# ETH_PHY_RGMII.net
KiCad netlist of a schematic drawn in Altium Designer
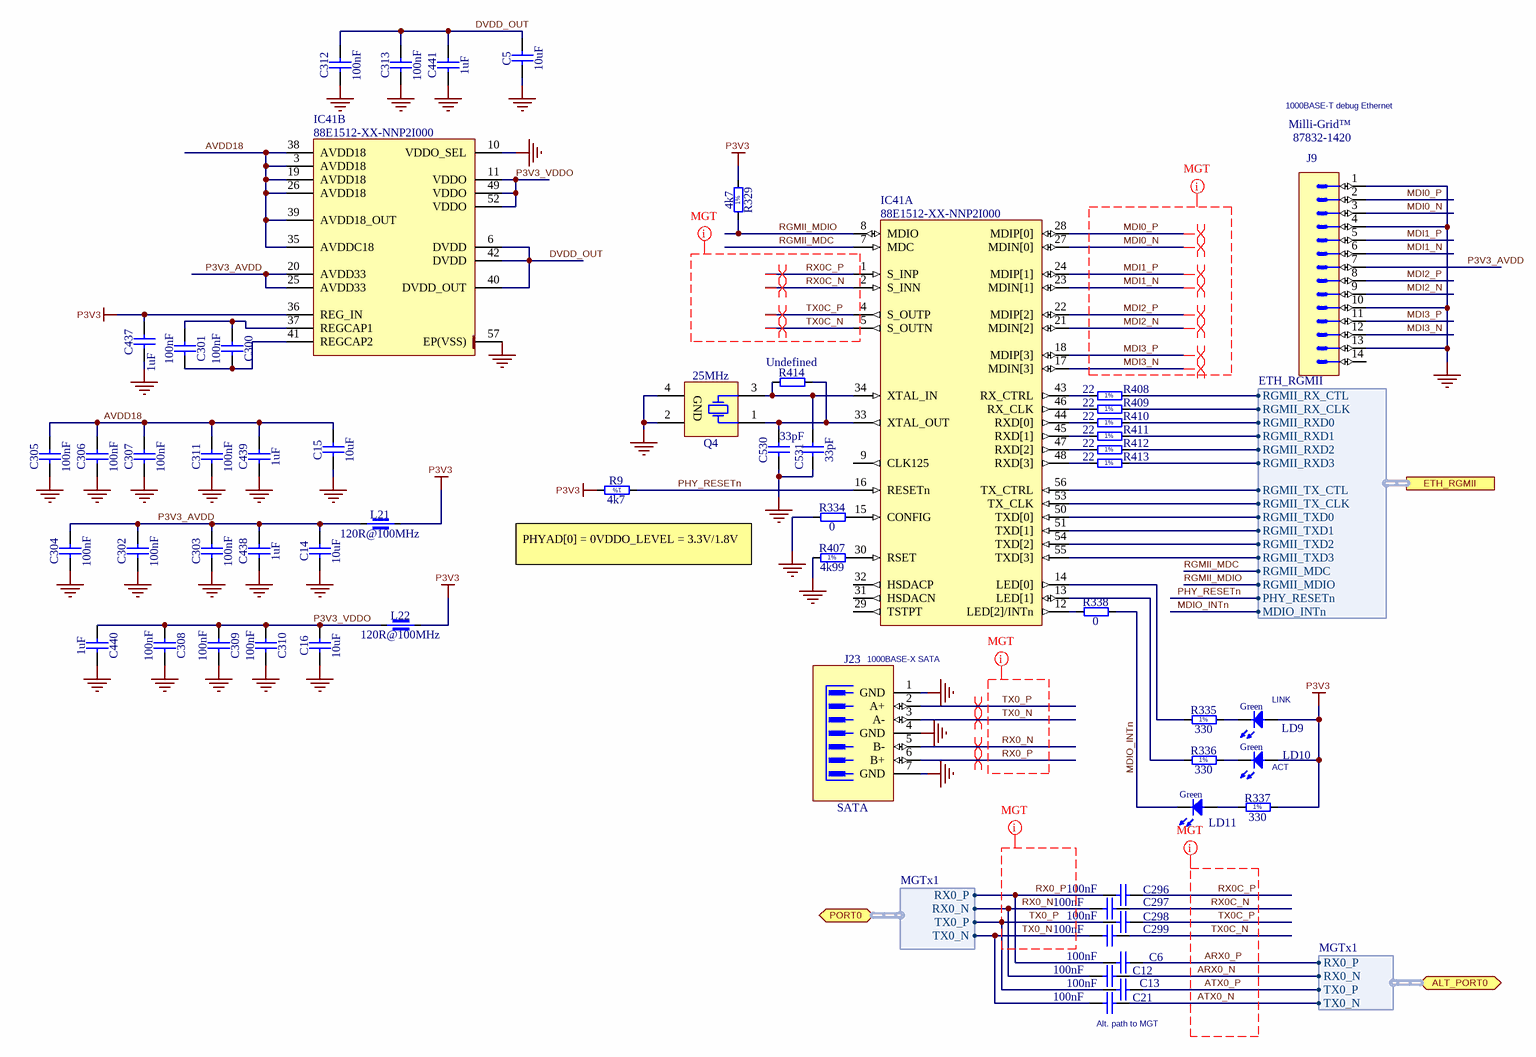
[diagram p0: ETH_PHY_RGMII.SchDoc]

(export (version "E")
  (design (tool "Eeschema 10.0.6"))
  (components
    (comp (ref "C5")
      (value "10uF")
      (footprint "CAPC1608X87N")
      (description "Non-polarised capacitor")
      (fields
        (field (name "MANUFACTURER PART NUMBER") "CC0603_10uF_6.3V_20%_X5R")
        (field (name "MANUFACTURER") "GENERIC")
        (field (name "AUTHOR") "CERN DEM JLC")
      )
      (libsource (lib "Capacitors") (part "Capacitor - non polarized"))
    )
    (comp (ref "C6")
      (value "100nF")
      (footprint "CAPC0603X33N")
      (description "Non-polarised capacitor")
      (fields
        (field (name "MANUFACTURER PART NUMBER") "CC0201_100NF_6.3V_10%_X5R")
        (field (name "MANUFACTURER") "GENERIC")
        (field (name "AUTHOR") "CERN DEM JLC")
      )
      (libsource (lib "Capacitors") (part "Capacitor - non polarized"))
    )
    (comp (ref "C12")
      (value "100nF")
      (footprint "CAPC0603X33N")
      (description "Non-polarised capacitor")
      (fields
        (field (name "MANUFACTURER PART NUMBER") "CC0201_100NF_6.3V_10%_X5R")
        (field (name "MANUFACTURER") "GENERIC")
        (field (name "AUTHOR") "CERN DEM JLC")
      )
      (libsource (lib "Capacitors") (part "Capacitor - non polarized"))
    )
    (comp (ref "C13")
      (value "100nF")
      (footprint "CAPC0603X33N")
      (description "Non-polarised capacitor")
      (fields
        (field (name "MANUFACTURER PART NUMBER") "CC0201_100NF_6.3V_10%_X5R")
        (field (name "MANUFACTURER") "GENERIC")
        (field (name "AUTHOR") "CERN DEM JLC")
      )
      (libsource (lib "Capacitors") (part "Capacitor - non polarized"))
    )
    (comp (ref "C14")
      (value "10uF")
      (footprint "CAPC1608X87N")
      (description "Non-polarised capacitor")
      (fields
        (field (name "MANUFACTURER PART NUMBER") "CC0603_10uF_6.3V_20%_X5R")
        (field (name "MANUFACTURER") "GENERIC")
        (field (name "AUTHOR") "CERN DEM JLC")
      )
      (libsource (lib "Capacitors") (part "Capacitor - non polarized"))
    )
    (comp (ref "C15")
      (value "10uF")
      (footprint "CAPC1608X87N")
      (description "Non-polarised capacitor")
      (fields
        (field (name "MANUFACTURER PART NUMBER") "CC0603_10uF_6.3V_20%_X5R")
        (field (name "MANUFACTURER") "GENERIC")
        (field (name "AUTHOR") "CERN DEM JLC")
      )
      (libsource (lib "Capacitors") (part "Capacitor - non polarized"))
    )
    (comp (ref "C16")
      (value "10uF")
      (footprint "CAPC1608X87N")
      (description "Non-polarised capacitor")
      (fields
        (field (name "MANUFACTURER PART NUMBER") "CC0603_10uF_6.3V_20%_X5R")
        (field (name "MANUFACTURER") "GENERIC")
        (field (name "AUTHOR") "CERN DEM JLC")
      )
      (libsource (lib "Capacitors") (part "Capacitor - non polarized"))
    )
    (comp (ref "C21")
      (value "100nF")
      (footprint "CAPC0603X33N")
      (description "Non-polarised capacitor")
      (fields
        (field (name "MANUFACTURER PART NUMBER") "CC0201_100NF_6.3V_10%_X5R")
        (field (name "MANUFACTURER") "GENERIC")
        (field (name "AUTHOR") "CERN DEM JLC")
      )
      (libsource (lib "Capacitors") (part "Capacitor - non polarized"))
    )
    (comp (ref "C296")
      (value "100nF")
      (footprint "CAPC0603X33N")
      (description "Non-polarised capacitor")
      (fields
        (field (name "MANUFACTURER PART NUMBER") "CC0201_100NF_6.3V_10%_X5R")
        (field (name "MANUFACTURER") "GENERIC")
        (field (name "AUTHOR") "CERN DEM JLC")
      )
      (libsource (lib "Capacitors") (part "Capacitor - non polarized"))
    )
    (comp (ref "C297")
      (value "100nF")
      (footprint "CAPC0603X33N")
      (description "Non-polarised capacitor")
      (fields
        (field (name "MANUFACTURER PART NUMBER") "CC0201_100NF_6.3V_10%_X5R")
        (field (name "MANUFACTURER") "GENERIC")
        (field (name "AUTHOR") "CERN DEM JLC")
      )
      (libsource (lib "Capacitors") (part "Capacitor - non polarized"))
    )
    (comp (ref "C298")
      (value "100nF")
      (footprint "CAPC0603X33N")
      (description "Non-polarised capacitor")
      (fields
        (field (name "MANUFACTURER PART NUMBER") "CC0201_100NF_6.3V_10%_X5R")
        (field (name "MANUFACTURER") "GENERIC")
        (field (name "AUTHOR") "CERN DEM JLC")
      )
      (libsource (lib "Capacitors") (part "Capacitor - non polarized"))
    )
    (comp (ref "C299")
      (value "100nF")
      (footprint "CAPC0603X33N")
      (description "Non-polarised capacitor")
      (fields
        (field (name "MANUFACTURER PART NUMBER") "CC0201_100NF_6.3V_10%_X5R")
        (field (name "MANUFACTURER") "GENERIC")
        (field (name "AUTHOR") "CERN DEM JLC")
      )
      (libsource (lib "Capacitors") (part "Capacitor - non polarized"))
    )
    (comp (ref "C300")
      (value "100nF")
      (footprint "CAPC0603X33N")
      (description "Non-polarised capacitor")
      (fields
        (field (name "MANUFACTURER PART NUMBER") "CC0201_100NF_6.3V_10%_X5R")
        (field (name "MANUFACTURER") "GENERIC")
        (field (name "AUTHOR") "CERN DEM JLC")
      )
      (libsource (lib "Capacitors") (part "Capacitor - non polarized"))
    )
    (comp (ref "C301")
      (value "100nF")
      (footprint "CAPC0603X33N")
      (description "Non-polarised capacitor")
      (fields
        (field (name "MANUFACTURER PART NUMBER") "CC0201_100NF_6.3V_10%_X5R")
        (field (name "MANUFACTURER") "GENERIC")
        (field (name "AUTHOR") "CERN DEM JLC")
      )
      (libsource (lib "Capacitors") (part "Capacitor - non polarized"))
    )
    (comp (ref "C302")
      (value "100nF")
      (footprint "CAPC0603X33N")
      (description "Non-polarised capacitor")
      (fields
        (field (name "MANUFACTURER PART NUMBER") "CC0201_100NF_6.3V_10%_X5R")
        (field (name "MANUFACTURER") "GENERIC")
        (field (name "AUTHOR") "CERN DEM JLC")
      )
      (libsource (lib "Capacitors") (part "Capacitor - non polarized"))
    )
    (comp (ref "C303")
      (value "100nF")
      (footprint "CAPC0603X33N")
      (description "Non-polarised capacitor")
      (fields
        (field (name "MANUFACTURER PART NUMBER") "CC0201_100NF_6.3V_10%_X5R")
        (field (name "MANUFACTURER") "GENERIC")
        (field (name "AUTHOR") "CERN DEM JLC")
      )
      (libsource (lib "Capacitors") (part "Capacitor - non polarized"))
    )
    (comp (ref "C304")
      (value "100nF")
      (footprint "CAPC0603X33N")
      (description "Non-polarised capacitor")
      (fields
        (field (name "MANUFACTURER PART NUMBER") "CC0201_100NF_6.3V_10%_X5R")
        (field (name "MANUFACTURER") "GENERIC")
        (field (name "AUTHOR") "CERN DEM JLC")
      )
      (libsource (lib "Capacitors") (part "Capacitor - non polarized"))
    )
    (comp (ref "C305")
      (value "100nF")
      (footprint "CAPC0603X33N")
      (description "Non-polarised capacitor")
      (fields
        (field (name "MANUFACTURER PART NUMBER") "CC0201_100NF_6.3V_10%_X5R")
        (field (name "MANUFACTURER") "GENERIC")
        (field (name "AUTHOR") "CERN DEM JLC")
      )
      (libsource (lib "Capacitors") (part "Capacitor - non polarized"))
    )
    (comp (ref "C306")
      (value "100nF")
      (footprint "CAPC0603X33N")
      (description "Non-polarised capacitor")
      (fields
        (field (name "MANUFACTURER PART NUMBER") "CC0201_100NF_6.3V_10%_X5R")
        (field (name "MANUFACTURER") "GENERIC")
        (field (name "AUTHOR") "CERN DEM JLC")
      )
      (libsource (lib "Capacitors") (part "Capacitor - non polarized"))
    )
    (comp (ref "C307")
      (value "100nF")
      (footprint "CAPC0603X33N")
      (description "Non-polarised capacitor")
      (fields
        (field (name "MANUFACTURER PART NUMBER") "CC0201_100NF_6.3V_10%_X5R")
        (field (name "MANUFACTURER") "GENERIC")
        (field (name "AUTHOR") "CERN DEM JLC")
      )
      (libsource (lib "Capacitors") (part "Capacitor - non polarized"))
    )
    (comp (ref "C308")
      (value "100nF")
      (footprint "CAPC0603X33N")
      (description "Non-polarised capacitor")
      (fields
        (field (name "MANUFACTURER PART NUMBER") "CC0201_100NF_6.3V_10%_X5R")
        (field (name "MANUFACTURER") "GENERIC")
        (field (name "AUTHOR") "CERN DEM JLC")
      )
      (libsource (lib "Capacitors") (part "Capacitor - non polarized"))
    )
    (comp (ref "C309")
      (value "100nF")
      (footprint "CAPC0603X33N")
      (description "Non-polarised capacitor")
      (fields
        (field (name "MANUFACTURER PART NUMBER") "CC0201_100NF_6.3V_10%_X5R")
        (field (name "MANUFACTURER") "GENERIC")
        (field (name "AUTHOR") "CERN DEM JLC")
      )
      (libsource (lib "Capacitors") (part "Capacitor - non polarized"))
    )
    (comp (ref "C310")
      (value "100nF")
      (footprint "CAPC0603X33N")
      (description "Non-polarised capacitor")
      (fields
        (field (name "MANUFACTURER PART NUMBER") "CC0201_100NF_6.3V_10%_X5R")
        (field (name "MANUFACTURER") "GENERIC")
        (field (name "AUTHOR") "CERN DEM JLC")
      )
      (libsource (lib "Capacitors") (part "Capacitor - non polarized"))
    )
    (comp (ref "C311")
      (value "100nF")
      (footprint "CAPC0603X33N")
      (description "Non-polarised capacitor")
      (fields
        (field (name "MANUFACTURER PART NUMBER") "CC0201_100NF_6.3V_10%_X5R")
        (field (name "MANUFACTURER") "GENERIC")
        (field (name "AUTHOR") "CERN DEM JLC")
      )
      (libsource (lib "Capacitors") (part "Capacitor - non polarized"))
    )
    (comp (ref "C312")
      (value "100nF")
      (footprint "CAPC0603X33N")
      (description "Non-polarised capacitor")
      (fields
        (field (name "MANUFACTURER PART NUMBER") "CC0201_100NF_6.3V_10%_X5R")
        (field (name "MANUFACTURER") "GENERIC")
        (field (name "AUTHOR") "CERN DEM JLC")
      )
      (libsource (lib "Capacitors") (part "Capacitor - non polarized"))
    )
    (comp (ref "C313")
      (value "100nF")
      (footprint "CAPC0603X33N")
      (description "Non-polarised capacitor")
      (fields
        (field (name "MANUFACTURER PART NUMBER") "CC0201_100NF_6.3V_10%_X5R")
        (field (name "MANUFACTURER") "GENERIC")
        (field (name "AUTHOR") "CERN DEM JLC")
      )
      (libsource (lib "Capacitors") (part "Capacitor - non polarized"))
    )
    (comp (ref "C437")
      (value "1uF")
      (footprint "CAPC1005X55N")
      (description "Non-polarised capacitor")
      (fields
        (field (name "MANUFACTURER PART NUMBER") "CC0402_1UF_16V_10%_X5R")
        (field (name "MANUFACTURER") "GENERIC")
        (field (name "AUTHOR") "CERN DEM JLC")
      )
      (libsource (lib "Capacitors") (part "Capacitor - non polarized"))
    )
    (comp (ref "C438")
      (value "1uF")
      (footprint "CAPC1005X55N")
      (description "Non-polarised capacitor")
      (fields
        (field (name "MANUFACTURER PART NUMBER") "CC0402_1UF_16V_10%_X5R")
        (field (name "MANUFACTURER") "GENERIC")
        (field (name "AUTHOR") "CERN DEM JLC")
      )
      (libsource (lib "Capacitors") (part "Capacitor - non polarized"))
    )
    (comp (ref "C439")
      (value "1uF")
      (footprint "CAPC1005X55N")
      (description "Non-polarised capacitor")
      (fields
        (field (name "MANUFACTURER PART NUMBER") "CC0402_1UF_16V_10%_X5R")
        (field (name "MANUFACTURER") "GENERIC")
        (field (name "AUTHOR") "CERN DEM JLC")
      )
      (libsource (lib "Capacitors") (part "Capacitor - non polarized"))
    )
    (comp (ref "C440")
      (value "1uF")
      (footprint "CAPC1005X55N")
      (description "Non-polarised capacitor")
      (fields
        (field (name "MANUFACTURER PART NUMBER") "CC0402_1UF_16V_10%_X5R")
        (field (name "MANUFACTURER") "GENERIC")
        (field (name "AUTHOR") "CERN DEM JLC")
      )
      (libsource (lib "Capacitors") (part "Capacitor - non polarized"))
    )
    (comp (ref "C441")
      (value "1uF")
      (footprint "CAPC1005X55N")
      (description "Non-polarised capacitor")
      (fields
        (field (name "MANUFACTURER PART NUMBER") "CC0402_1UF_16V_10%_X5R")
        (field (name "MANUFACTURER") "GENERIC")
        (field (name "AUTHOR") "CERN DEM JLC")
      )
      (libsource (lib "Capacitors") (part "Capacitor - non polarized"))
    )
    (comp (ref "C530")
      (value "33pF")
      (footprint "CAPC1005X55N")
      (description "Non-polarised capacitor")
      (fields
        (field (name "MANUFACTURER PART NUMBER") "CC0402_33PF_50V_5%_C0G")
        (field (name "MANUFACTURER") "GENERIC")
        (field (name "AUTHOR") "CERN DEM JLC")
      )
      (libsource (lib "Capacitors") (part "Capacitor - non polarized"))
    )
    (comp (ref "C531")
      (value "33pF")
      (footprint "CAPC1005X55N")
      (description "Non-polarised capacitor")
      (fields
        (field (name "MANUFACTURER PART NUMBER") "CC0402_33PF_50V_5%_C0G")
        (field (name "MANUFACTURER") "GENERIC")
        (field (name "AUTHOR") "CERN DEM JLC")
      )
      (libsource (lib "Capacitors") (part "Capacitor - non polarized"))
    )
    (comp (ref "IC41")
      (value "88E1512-XX-NNP2I000")
      (footprint "QFN50P800X800X100-57N-S437")
      (description "Alaska Integrated 10/100/1000 Mbps Energy Efficient Ethernet Transceiver")
      (fields (field (name "MANUFACTURER") "MARVELL  TECHNOLOGY") (field (name "AUTHOR") "CERN DEM JLC"))
      (libsource (lib "ICs And Semiconductors") (part "88E1512-XX-NNP2I000"))
    )
    (comp (ref "J9")
      (value "Milli-Grid™")
      (footprint "MOLEX_87832-1420")
      (description "Connector 14 Male")
      (fields
        (field (name "MANUFACTURER PART NUMBER") "87832-1420")
        (field (name "MANUFACTURER") "MOLEX")
        (field (name "PART NUMBER") "MOLEX_87832-1420")
        (field (name "AUTHOR") "CERN DEM JLC")
      )
      (libsource (lib "Connectors") (part "Connector 14 Male"))
    )
    (comp (ref "J23")
      (value "SATA")
      (footprint "MOLEX_67800-5005")
      (description "7 Pin SATA Receptacle")
      (fields
        (field (name "PART NUMBER") "MOLEX_67800-5005")
        (field (name "MANUFACTURER") "MOLEX")
        (field (name "AUTHOR") "CERN DEM MR")
      )
      (libsource (lib "Connectors") (part "Connector SATA 7 Male"))
    )
    (comp (ref "L21")
      (value "120R@100MHz")
      (footprint "INDC1005X55N")
      (fields
        (field (name "MANUFACTURER PART NUMBER") "BLM15PX121SN1D")
        (field (name "MANUFACTURER") "MURATA")
        (field (name "PART NUMBER") "IND0402_MURATA_BLM15PX121SN1D")
        (field (name "AUTHOR") "CERN DEM JMW")
      )
      (libsource (lib "") (part "Ferrite Bead_1"))
    )
    (comp (ref "L22")
      (value "120R@100MHz")
      (footprint "INDC1005X55N")
      (fields
        (field (name "MANUFACTURER PART NUMBER") "BLM15PX121SN1D")
        (field (name "MANUFACTURER") "MURATA")
        (field (name "PART NUMBER") "IND0402_MURATA_BLM15PX121SN1D")
        (field (name "AUTHOR") "CERN DEM JMW")
      )
      (libsource (lib "Inductors & Transformers") (part "Ferrite Bead"))
    )
    (comp (ref "LD9")
      (value "Green")
      (footprint "LED_AVAGO_HSME-C120")
      (description "LED Green 1C 2A")
      (fields
        (field (name "MANUFACTURER PART NUMBER") "HSME-C120")
        (field (name "MANUFACTURER") "AVAGO TECHNOLOGIES")
        (field (name "AUTHOR") "CERN DEM JMW")
      )
      (libsource (lib "ICs And Semiconductors") (part "LED Green 1C 2A"))
    )
    (comp (ref "LD10")
      (value "Green")
      (footprint "LED_AVAGO_HSME-C120")
      (description "LED Green 1C 2A")
      (fields
        (field (name "MANUFACTURER PART NUMBER") "HSME-C120")
        (field (name "MANUFACTURER") "AVAGO TECHNOLOGIES")
        (field (name "AUTHOR") "CERN DEM JMW")
      )
      (libsource (lib "ICs And Semiconductors") (part "LED Green 1C 2A"))
    )
    (comp (ref "LD11")
      (value "Green")
      (footprint "LED_AVAGO_HSME-C120")
      (description "LED Green 1C 2A")
      (fields
        (field (name "MANUFACTURER PART NUMBER") "HSME-C120")
        (field (name "MANUFACTURER") "AVAGO TECHNOLOGIES")
        (field (name "AUTHOR") "CERN DEM JMW")
      )
      (libsource (lib "ICs And Semiconductors") (part "LED Green 1C 2A"))
    )
    (comp (ref "Q4")
      (value "25MHz")
      (footprint "XTAL_TXC_8Y")
      (description "Crystal 4 pins 1=XTAL Control 2=GND3=XTAL 4=GND")
      (fields
        (field (name "MANUFACTURER PART NUMBER") "8Y-25.000MAAJ-T")
        (field (name "MANUFACTURER") "TXC CORPORATION")
        (field (name "AUTHOR") "CERN DEM JLC")
      )
      (libsource (lib "ICs And Semiconductors") (part "Quartz Crystal 1X 2GND 3X 4GND"))
    )
    (comp (ref "R9")
      (value "4k7")
      (footprint "RESC1005X40N")
      (description "Resistor - 1%")
      (fields
        (field (name "MANUFACTURER PART NUMBER") "R0402_4K7_1%_0.0625W_100PPM")
        (field (name "MANUFACTURER") "GENERIC")
        (field (name "AUTHOR") "CERN DEM JLC")
      )
      (libsource (lib "Resistors") (part "Resistor - 1%"))
    )
    (comp (ref "R329")
      (value "4k7")
      (footprint "RESC1005X40N")
      (description "Resistor - 1%")
      (fields
        (field (name "MANUFACTURER PART NUMBER") "R0402_4K7_1%_0.0625W_100PPM")
        (field (name "MANUFACTURER") "GENERIC")
        (field (name "AUTHOR") "CERN DEM JLC")
      )
      (libsource (lib "Resistors") (part "Resistor - 1%"))
    )
    (comp (ref "R334")
      (value "0")
      (footprint "RESC1005X40N")
      (description "Resistor")
      (fields
        (field (name "MANUFACTURER PART NUMBER") "R0402_0R_JUMPER")
        (field (name "MANUFACTURER") "GENERIC")
        (field (name "AUTHOR") "CERN DEM JLC")
      )
      (libsource (lib "Resistors") (part "Resistor"))
    )
    (comp (ref "R335")
      (value "330")
      (footprint "RESC1005X40N")
      (description "Resistor - 1%")
      (fields
        (field (name "MANUFACTURER PART NUMBER") "R0402_330R_1%_0.0625W_100PPM")
        (field (name "MANUFACTURER") "GENERIC")
        (field (name "AUTHOR") "CERN DEM JLC")
      )
      (libsource (lib "Resistors") (part "Resistor - 1%"))
    )
    (comp (ref "R336")
      (value "330")
      (footprint "RESC1005X40N")
      (description "Resistor - 1%")
      (fields
        (field (name "MANUFACTURER PART NUMBER") "R0402_330R_1%_0.0625W_100PPM")
        (field (name "MANUFACTURER") "GENERIC")
        (field (name "AUTHOR") "CERN DEM JLC")
      )
      (libsource (lib "Resistors") (part "Resistor - 1%"))
    )
    (comp (ref "R337")
      (value "330")
      (footprint "RESC1005X40N")
      (description "Resistor - 1%")
      (fields
        (field (name "MANUFACTURER PART NUMBER") "R0402_330R_1%_0.0625W_100PPM")
        (field (name "MANUFACTURER") "GENERIC")
        (field (name "AUTHOR") "CERN DEM JLC")
      )
      (libsource (lib "Resistors") (part "Resistor - 1%"))
    )
    (comp (ref "R338")
      (value "0")
      (footprint "RESC1005X40N")
      (description "Resistor")
      (fields
        (field (name "MANUFACTURER PART NUMBER") "R0402_0R_JUMPER")
        (field (name "MANUFACTURER") "GENERIC")
        (field (name "AUTHOR") "CERN DEM JLC")
      )
      (libsource (lib "Resistors") (part "Resistor"))
    )
    (comp (ref "R407")
      (value "4k99")
      (footprint "RESC1608X55N")
      (description "Resistor - 1%")
      (fields
        (field (name "MANUFACTURER PART NUMBER") "R0603_4K99_1%_0.063W_50PPM")
        (field (name "MANUFACTURER") "GENERIC")
        (field (name "AUTHOR") "CERN DEM JLC")
      )
      (libsource (lib "Resistors") (part "Resistor - 1%"))
    )
    (comp (ref "R408")
      (value "22")
      (footprint "RESC1005X40N")
      (description "Resistor - 1%")
      (fields
        (field (name "MANUFACTURER PART NUMBER") "R0402_22R_1%_0.0625W_100PPM")
        (field (name "MANUFACTURER") "GENERIC")
        (field (name "AUTHOR") "CERN DEM JLC")
      )
      (libsource (lib "Resistors") (part "Resistor - 1%"))
    )
    (comp (ref "R409")
      (value "22")
      (footprint "RESC1005X40N")
      (description "Resistor - 1%")
      (fields
        (field (name "MANUFACTURER PART NUMBER") "R0402_22R_1%_0.0625W_100PPM")
        (field (name "MANUFACTURER") "GENERIC")
        (field (name "AUTHOR") "CERN DEM JLC")
      )
      (libsource (lib "Resistors") (part "Resistor - 1%"))
    )
    (comp (ref "R410")
      (value "22")
      (footprint "RESC1005X40N")
      (description "Resistor - 1%")
      (fields
        (field (name "MANUFACTURER PART NUMBER") "R0402_22R_1%_0.0625W_100PPM")
        (field (name "MANUFACTURER") "GENERIC")
        (field (name "AUTHOR") "CERN DEM JLC")
      )
      (libsource (lib "Resistors") (part "Resistor - 1%"))
    )
    (comp (ref "R411")
      (value "22")
      (footprint "RESC1005X40N")
      (description "Resistor - 1%")
      (fields
        (field (name "MANUFACTURER PART NUMBER") "R0402_22R_1%_0.0625W_100PPM")
        (field (name "MANUFACTURER") "GENERIC")
        (field (name "AUTHOR") "CERN DEM JLC")
      )
      (libsource (lib "Resistors") (part "Resistor - 1%"))
    )
    (comp (ref "R412")
      (value "22")
      (footprint "RESC1005X40N")
      (description "Resistor - 1%")
      (fields
        (field (name "MANUFACTURER PART NUMBER") "R0402_22R_1%_0.0625W_100PPM")
        (field (name "MANUFACTURER") "GENERIC")
        (field (name "AUTHOR") "CERN DEM JLC")
      )
      (libsource (lib "Resistors") (part "Resistor - 1%"))
    )
    (comp (ref "R413")
      (value "22")
      (footprint "RESC1005X40N")
      (description "Resistor - 1%")
      (fields
        (field (name "MANUFACTURER PART NUMBER") "R0402_22R_1%_0.0625W_100PPM")
        (field (name "MANUFACTURER") "GENERIC")
        (field (name "AUTHOR") "CERN DEM JLC")
      )
      (libsource (lib "Resistors") (part "Resistor - 1%"))
    )
    (comp (ref "R414")
      (value "Undefined")
      (footprint "RESC1005X40N")
      (description "Resistor")
      (fields
        (field (name "MANUFACTURER PART NUMBER") "R0402_NO-VALUE")
        (field (name "AUTHOR") "CERN DEM JLC")
      )
      (libsource (lib "Resistors") (part "Resistor"))
    )
  )
  (nets
    (net (code "3") (name "/ARX0_N") (class "Default")
      (node (ref "C12") (pin "2") (pinfunction "2_2") (pintype "passive"))
    )
    (net (code "4") (name "/ARX0_P") (class "Default")
      (node (ref "C6") (pin "2") (pinfunction "2_2") (pintype "passive"))
    )
    (net (code "5") (name "/ATX0_N") (class "Default")
      (node (ref "C21") (pin "2") (pinfunction "2_2") (pintype "passive"))
    )
    (net (code "6") (name "/ATX0_P") (class "Default")
      (node (ref "C13") (pin "2") (pinfunction "2_2") (pintype "passive"))
    )
    (net (code "7") (name "/AVDD18") (class "Default")
      (node (ref "C15") (pin "2") (pinfunction "2_2") (pintype "passive"))
      (node (ref "C305") (pin "2") (pinfunction "2_2") (pintype "passive"))
      (node (ref "C306") (pin "2") (pinfunction "2_2") (pintype "passive"))
      (node (ref "C307") (pin "2") (pinfunction "2_2") (pintype "passive"))
      (node (ref "C311") (pin "2") (pinfunction "2_2") (pintype "passive"))
      (node (ref "C439") (pin "2") (pinfunction "2_2") (pintype "passive"))
      (node (ref "IC41") (pin "19") (pinfunction "AVDD18_19") (pintype "power_in"))
      (node (ref "IC41") (pin "26") (pinfunction "AVDD18_26") (pintype "power_in"))
      (node (ref "IC41") (pin "3") (pinfunction "AVDD18_3") (pintype "power_in"))
      (node (ref "IC41") (pin "35") (pinfunction "AVDDC18_35") (pintype "power_in"))
      (node (ref "IC41") (pin "38") (pinfunction "AVDD18_38") (pintype "power_in"))
      (node (ref "IC41") (pin "39") (pinfunction "AVDD18_OUT_39") (pintype "power_in"))
    )
    (net (code "8") (name "/DVDD_OUT") (class "Default")
      (node (ref "C312") (pin "2") (pinfunction "2_2") (pintype "passive"))
      (node (ref "C313") (pin "2") (pinfunction "2_2") (pintype "passive"))
      (node (ref "C441") (pin "2") (pinfunction "2_2") (pintype "passive"))
      (node (ref "C5") (pin "2") (pinfunction "2_2") (pintype "passive"))
      (node (ref "IC41") (pin "40") (pinfunction "DVDD_OUT_40") (pintype "power_in"))
      (node (ref "IC41") (pin "42") (pinfunction "DVDD_42") (pintype "power_in"))
      (node (ref "IC41") (pin "6") (pinfunction "DVDD_6") (pintype "power_in"))
    )
    (net (code "9") (name "/MDI0_N") (class "Default")
      (node (ref "IC41") (pin "27") (pinfunction "MDIN[0]_27") (pintype "bidirectional"))
      (node (ref "J9") (pin "3") (pinfunction "3_3") (pintype "bidirectional"))
    )
    (net (code "10") (name "/MDI0_P") (class "Default")
      (node (ref "IC41") (pin "28") (pinfunction "MDIP[0]_28") (pintype "bidirectional"))
      (node (ref "J9") (pin "2") (pinfunction "2_2") (pintype "bidirectional"))
    )
    (net (code "11") (name "/MDI1_N") (class "Default")
      (node (ref "IC41") (pin "23") (pinfunction "MDIN[1]_23") (pintype "bidirectional"))
      (node (ref "J9") (pin "6") (pinfunction "6_6") (pintype "bidirectional"))
    )
    (net (code "12") (name "/MDI1_P") (class "Default")
      (node (ref "IC41") (pin "24") (pinfunction "MDIP[1]_24") (pintype "bidirectional"))
      (node (ref "J9") (pin "5") (pinfunction "5_5") (pintype "bidirectional"))
    )
    (net (code "13") (name "/MDI2_N") (class "Default")
      (node (ref "IC41") (pin "21") (pinfunction "MDIN[2]_21") (pintype "bidirectional"))
      (node (ref "J9") (pin "9") (pinfunction "9_9") (pintype "bidirectional"))
    )
    (net (code "14") (name "/MDI2_P") (class "Default")
      (node (ref "IC41") (pin "22") (pinfunction "MDIP[2]_22") (pintype "bidirectional"))
      (node (ref "J9") (pin "8") (pinfunction "8_8") (pintype "bidirectional"))
    )
    (net (code "15") (name "/MDI3_N") (class "Default")
      (node (ref "IC41") (pin "17") (pinfunction "MDIN[3]_17") (pintype "bidirectional"))
      (node (ref "J9") (pin "12") (pinfunction "12_12") (pintype "bidirectional"))
    )
    (net (code "16") (name "/MDI3_P") (class "Default")
      (node (ref "IC41") (pin "18") (pinfunction "MDIP[3]_18") (pintype "bidirectional"))
      (node (ref "J9") (pin "11") (pinfunction "11_11") (pintype "bidirectional"))
    )
    (net (code "17") (name "/MDIO_INTn") (class "Default")
      (node (ref "LD11") (pin "1") (pinfunction "C_1") (pintype "passive"))
      (node (ref "R338") (pin "2") (pinfunction "2_2") (pintype "passive"))
    )
    (net (code "18") (name "/P3V3_AVDD") (class "Default")
      (node (ref "C14") (pin "2") (pinfunction "2_2") (pintype "passive"))
      (node (ref "C302") (pin "2") (pinfunction "2_2") (pintype "passive"))
      (node (ref "C303") (pin "2") (pinfunction "2_2") (pintype "passive"))
      (node (ref "C304") (pin "2") (pinfunction "2_2") (pintype "passive"))
      (node (ref "C438") (pin "2") (pinfunction "2_2") (pintype "passive"))
      (node (ref "IC41") (pin "20") (pinfunction "AVDD33_20") (pintype "power_in"))
      (node (ref "IC41") (pin "25") (pinfunction "AVDD33_25") (pintype "power_in"))
      (node (ref "J9") (pin "7") (pinfunction "7_7") (pintype "bidirectional"))
      (node (ref "L21") (pin "1") (pinfunction "1_1") (pintype "passive"))
    )
    (net (code "19") (name "/P3V3_VDDO") (class "Default")
      (node (ref "C16") (pin "2") (pinfunction "2_2") (pintype "passive"))
      (node (ref "C308") (pin "2") (pinfunction "2_2") (pintype "passive"))
      (node (ref "C309") (pin "2") (pinfunction "2_2") (pintype "passive"))
      (node (ref "C310") (pin "2") (pinfunction "2_2") (pintype "passive"))
      (node (ref "C440") (pin "2") (pinfunction "2_2") (pintype "passive"))
      (node (ref "IC41") (pin "11") (pinfunction "VDDO_11") (pintype "power_in"))
      (node (ref "IC41") (pin "49") (pinfunction "VDDO_49") (pintype "power_in"))
      (node (ref "IC41") (pin "52") (pinfunction "VDDO_52") (pintype "power_in"))
      (node (ref "L22") (pin "2") (pinfunction "2_2") (pintype "passive"))
    )
    (net (code "20") (name "/PHY_RESETn") (class "Default")
      (node (ref "IC41") (pin "16") (pinfunction "RESETn_16") (pintype "input"))
      (node (ref "R9") (pin "1") (pinfunction "1_1") (pintype "passive"))
    )
    (net (code "21") (name "/RGMII_MDC") (class "Default")
      (node (ref "IC41") (pin "7") (pinfunction "MDC_7") (pintype "input"))
    )
    (net (code "22") (name "/RGMII_MDIO") (class "Default")
      (node (ref "IC41") (pin "8") (pinfunction "MDIO_8") (pintype "bidirectional"))
      (node (ref "R329") (pin "1") (pinfunction "1_1") (pintype "passive"))
    )
    (net (code "23") (name "/RGMII_RXD0") (class "Default")
      (node (ref "R410") (pin "2") (pinfunction "2_2") (pintype "passive"))
    )
    (net (code "24") (name "/RGMII_RXD1") (class "Default")
      (node (ref "R411") (pin "2") (pinfunction "2_2") (pintype "passive"))
    )
    (net (code "25") (name "/RGMII_RXD2") (class "Default")
      (node (ref "R412") (pin "2") (pinfunction "2_2") (pintype "passive"))
    )
    (net (code "26") (name "/RGMII_RXD3") (class "Default")
      (node (ref "R413") (pin "2") (pinfunction "2_2") (pintype "passive"))
    )
    (net (code "27") (name "/RGMII_RX_CLK") (class "Default")
      (node (ref "R409") (pin "2") (pinfunction "2_2") (pintype "passive"))
    )
    (net (code "28") (name "/RGMII_RX_CTL") (class "Default")
      (node (ref "R408") (pin "2") (pinfunction "2_2") (pintype "passive"))
    )
    (net (code "29") (name "/RGMII_TXD0") (class "Default")
      (node (ref "IC41") (pin "50") (pinfunction "TXD[0]_50") (pintype "input"))
    )
    (net (code "30") (name "/RGMII_TXD1") (class "Default")
      (node (ref "IC41") (pin "51") (pinfunction "TXD[1]_51") (pintype "input"))
    )
    (net (code "31") (name "/RGMII_TXD2") (class "Default")
      (node (ref "IC41") (pin "54") (pinfunction "TXD[2]_54") (pintype "input"))
    )
    (net (code "32") (name "/RGMII_TXD3") (class "Default")
      (node (ref "IC41") (pin "55") (pinfunction "TXD[3]_55") (pintype "input"))
    )
    (net (code "33") (name "/RGMII_TX_CLK") (class "Default")
      (node (ref "IC41") (pin "53") (pinfunction "TX_CLK_53") (pintype "input"))
    )
    (net (code "34") (name "/RGMII_TX_CTL") (class "Default")
      (node (ref "IC41") (pin "56") (pinfunction "TX_CTRL_56") (pintype "input"))
    )
    (net (code "35") (name "/RX0C_N") (class "Default")
      (node (ref "C297") (pin "2") (pinfunction "2_2") (pintype "passive"))
      (node (ref "IC41") (pin "2") (pinfunction "S_INN_2") (pintype "input"))
    )
    (net (code "36") (name "/RX0C_P") (class "Default")
      (node (ref "C296") (pin "2") (pinfunction "2_2") (pintype "passive"))
      (node (ref "IC41") (pin "1") (pinfunction "S_INP_1") (pintype "input"))
    )
    (net (code "37") (name "/RX0_N") (class "Default")
      (node (ref "C12") (pin "1") (pinfunction "1_1") (pintype "passive"))
      (node (ref "C297") (pin "1") (pinfunction "1_1") (pintype "passive"))
      (node (ref "J23") (pin "5") (pinfunction "B-_5") (pintype "bidirectional"))
    )
    (net (code "38") (name "/RX0_P") (class "Default")
      (node (ref "C296") (pin "1") (pinfunction "1_1") (pintype "passive"))
      (node (ref "C6") (pin "1") (pinfunction "1_1") (pintype "passive"))
      (node (ref "J23") (pin "6") (pinfunction "B+_6") (pintype "bidirectional"))
    )
    (net (code "39") (name "/TX0C_N") (class "Default")
      (node (ref "C299") (pin "2") (pinfunction "2_2") (pintype "passive"))
      (node (ref "IC41") (pin "5") (pinfunction "S_OUTN_5") (pintype "output"))
    )
    (net (code "40") (name "/TX0C_P") (class "Default")
      (node (ref "C298") (pin "2") (pinfunction "2_2") (pintype "passive"))
      (node (ref "IC41") (pin "4") (pinfunction "S_OUTP_4") (pintype "output"))
    )
    (net (code "41") (name "/TX0_N") (class "Default")
      (node (ref "C21") (pin "1") (pinfunction "1_1") (pintype "passive"))
      (node (ref "C299") (pin "1") (pinfunction "1_1") (pintype "passive"))
      (node (ref "J23") (pin "3") (pinfunction "A-_3") (pintype "bidirectional"))
    )
    (net (code "42") (name "/TX0_P") (class "Default")
      (node (ref "C13") (pin "1") (pinfunction "1_1") (pintype "passive"))
      (node (ref "C298") (pin "1") (pinfunction "1_1") (pintype "passive"))
      (node (ref "J23") (pin "2") (pinfunction "A+_2") (pintype "bidirectional"))
    )
    (net (code "45") (name "GND") (class "Default")
      (node (ref "C14") (pin "1") (pinfunction "1_1") (pintype "passive"))
      (node (ref "C15") (pin "1") (pinfunction "1_1") (pintype "passive"))
      (node (ref "C16") (pin "1") (pinfunction "1_1") (pintype "passive"))
      (node (ref "C302") (pin "1") (pinfunction "1_1") (pintype "passive"))
      (node (ref "C303") (pin "1") (pinfunction "1_1") (pintype "passive"))
      (node (ref "C304") (pin "1") (pinfunction "1_1") (pintype "passive"))
      (node (ref "C305") (pin "1") (pinfunction "1_1") (pintype "passive"))
      (node (ref "C306") (pin "1") (pinfunction "1_1") (pintype "passive"))
      (node (ref "C307") (pin "1") (pinfunction "1_1") (pintype "passive"))
      (node (ref "C308") (pin "1") (pinfunction "1_1") (pintype "passive"))
      (node (ref "C309") (pin "1") (pinfunction "1_1") (pintype "passive"))
      (node (ref "C310") (pin "1") (pinfunction "1_1") (pintype "passive"))
      (node (ref "C311") (pin "1") (pinfunction "1_1") (pintype "passive"))
      (node (ref "C312") (pin "1") (pinfunction "1_1") (pintype "passive"))
      (node (ref "C313") (pin "1") (pinfunction "1_1") (pintype "passive"))
      (node (ref "C437") (pin "1") (pinfunction "1_1") (pintype "passive"))
      (node (ref "C438") (pin "1") (pinfunction "1_1") (pintype "passive"))
      (node (ref "C439") (pin "1") (pinfunction "1_1") (pintype "passive"))
      (node (ref "C440") (pin "1") (pinfunction "1_1") (pintype "passive"))
      (node (ref "C441") (pin "1") (pinfunction "1_1") (pintype "passive"))
      (node (ref "C5") (pin "1") (pinfunction "1_1") (pintype "passive"))
      (node (ref "C530") (pin "1") (pinfunction "1_1") (pintype "passive"))
      (node (ref "C531") (pin "1") (pinfunction "1_1") (pintype "passive"))
      (node (ref "IC41") (pin "10") (pinfunction "VDDO_SEL_10") (pintype "power_in"))
      (node (ref "IC41") (pin "57") (pinfunction "EP(VSS)_57") (pintype "power_in"))
      (node (ref "J23") (pin "1") (pinfunction "GND_1") (pintype "power_in"))
      (node (ref "J23") (pin "4") (pinfunction "GND_4") (pintype "power_in"))
      (node (ref "J23") (pin "7") (pinfunction "GND_7") (pintype "power_in"))
      (node (ref "J9") (pin "1") (pinfunction "1_1") (pintype "bidirectional"))
      (node (ref "J9") (pin "10") (pinfunction "10_10") (pintype "bidirectional"))
      (node (ref "J9") (pin "13") (pinfunction "13_13") (pintype "bidirectional"))
      (node (ref "J9") (pin "4") (pinfunction "4_4") (pintype "bidirectional"))
      (node (ref "Q4") (pin "2") (pinfunction "GND_2") (pintype "power_in"))
      (node (ref "Q4") (pin "4") (pinfunction "GND_4") (pintype "power_in"))
      (node (ref "R334") (pin "1") (pinfunction "1_1") (pintype "passive"))
      (node (ref "R407") (pin "1") (pinfunction "1_1") (pintype "passive"))
    )
    (net (code "46") (name "Net-(IC41A-CONFIG)") (class "Default")
      (node (ref "IC41") (pin "15") (pinfunction "CONFIG_15") (pintype "input"))
      (node (ref "R334") (pin "2") (pinfunction "2_2") (pintype "passive"))
    )
    (net (code "47") (name "Net-(IC41A-LED[0])") (class "Default")
      (node (ref "IC41") (pin "14") (pinfunction "LED[0]_14") (pintype "output"))
      (node (ref "R335") (pin "1") (pinfunction "1_1") (pintype "passive"))
    )
    (net (code "48") (name "Net-(IC41A-LED[1])") (class "Default")
      (node (ref "IC41") (pin "13") (pinfunction "LED[1]_13") (pintype "bidirectional"))
      (node (ref "R336") (pin "1") (pinfunction "1_1") (pintype "passive"))
    )
    (net (code "49") (name "Net-(IC41A-LED[2]{slash}INTn)") (class "Default")
      (node (ref "IC41") (pin "12") (pinfunction "LED[2]/INTn_12") (pintype "output"))
      (node (ref "R338") (pin "1") (pinfunction "1_1") (pintype "passive"))
    )
    (net (code "50") (name "Net-(IC41A-RSET)") (class "Default")
      (node (ref "IC41") (pin "30") (pinfunction "RSET_30") (pintype "input"))
      (node (ref "R407") (pin "2") (pinfunction "2_2") (pintype "passive"))
    )
    (net (code "51") (name "Net-(IC41A-RXD[0])") (class "Default")
      (node (ref "IC41") (pin "44") (pinfunction "RXD[0]_44") (pintype "output"))
      (node (ref "R410") (pin "1") (pinfunction "1_1") (pintype "passive"))
    )
    (net (code "52") (name "Net-(IC41A-RXD[1])") (class "Default")
      (node (ref "IC41") (pin "45") (pinfunction "RXD[1]_45") (pintype "output"))
      (node (ref "R411") (pin "1") (pinfunction "1_1") (pintype "passive"))
    )
    (net (code "53") (name "Net-(IC41A-RXD[2])") (class "Default")
      (node (ref "IC41") (pin "47") (pinfunction "RXD[2]_47") (pintype "output"))
      (node (ref "R412") (pin "1") (pinfunction "1_1") (pintype "passive"))
    )
    (net (code "54") (name "Net-(IC41A-RXD[3])") (class "Default")
      (node (ref "IC41") (pin "48") (pinfunction "RXD[3]_48") (pintype "output"))
      (node (ref "R413") (pin "1") (pinfunction "1_1") (pintype "passive"))
    )
    (net (code "55") (name "Net-(IC41A-RX_CLK)") (class "Default")
      (node (ref "IC41") (pin "46") (pinfunction "RX_CLK_46") (pintype "output"))
      (node (ref "R409") (pin "1") (pinfunction "1_1") (pintype "passive"))
    )
    (net (code "56") (name "Net-(IC41A-RX_CTRL)") (class "Default")
      (node (ref "IC41") (pin "43") (pinfunction "RX_CTRL_43") (pintype "output"))
      (node (ref "R408") (pin "1") (pinfunction "1_1") (pintype "passive"))
    )
    (net (code "57") (name "Net-(IC41A-XTAL_IN)") (class "Default")
      (node (ref "C531") (pin "2") (pinfunction "2_2") (pintype "passive"))
      (node (ref "IC41") (pin "34") (pinfunction "XTAL_IN_34") (pintype "input"))
      (node (ref "Q4") (pin "3") (pinfunction "X_3") (pintype "passive"))
      (node (ref "R414") (pin "1") (pinfunction "1_1") (pintype "passive"))
    )
    (net (code "58") (name "Net-(IC41A-XTAL_OUT)") (class "Default")
      (node (ref "C530") (pin "2") (pinfunction "2_2") (pintype "passive"))
      (node (ref "IC41") (pin "33") (pinfunction "XTAL_OUT_33") (pintype "output"))
      (node (ref "Q4") (pin "1") (pinfunction "X_1") (pintype "passive"))
      (node (ref "R414") (pin "2") (pinfunction "2_2") (pintype "passive"))
    )
    (net (code "59") (name "Net-(IC41B-REGCAP1)") (class "Default")
      (node (ref "C300") (pin "2") (pinfunction "2_2") (pintype "passive"))
      (node (ref "C301") (pin "2") (pinfunction "2_2") (pintype "passive"))
      (node (ref "IC41") (pin "37") (pinfunction "REGCAP1_37") (pintype "passive"))
    )
    (net (code "60") (name "Net-(IC41B-REGCAP2)") (class "Default")
      (node (ref "C300") (pin "1") (pinfunction "1_1") (pintype "passive"))
      (node (ref "C301") (pin "1") (pinfunction "1_1") (pintype "passive"))
      (node (ref "IC41") (pin "41") (pinfunction "REGCAP2_41") (pintype "passive"))
    )
    (net (code "61") (name "Net-(LD9-C)") (class "Default")
      (node (ref "LD9") (pin "1") (pinfunction "C_1") (pintype "passive"))
      (node (ref "R335") (pin "2") (pinfunction "2_2") (pintype "passive"))
    )
    (net (code "62") (name "Net-(LD10-C)") (class "Default")
      (node (ref "LD10") (pin "1") (pinfunction "C_1") (pintype "passive"))
      (node (ref "R336") (pin "2") (pinfunction "2_2") (pintype "passive"))
    )
    (net (code "63") (name "Net-(LD11-A)") (class "Default")
      (node (ref "LD11") (pin "2") (pinfunction "A_2") (pintype "passive"))
      (node (ref "R337") (pin "1") (pinfunction "1_1") (pintype "passive"))
    )
    (net (code "64") (name "P3V3") (class "Default")
      (node (ref "C437") (pin "2") (pinfunction "2_2") (pintype "passive"))
      (node (ref "IC41") (pin "36") (pinfunction "REG_IN_36") (pintype "power_in"))
      (node (ref "L21") (pin "2") (pinfunction "2_2") (pintype "passive"))
      (node (ref "L22") (pin "1") (pinfunction "1_1") (pintype "passive"))
      (node (ref "LD10") (pin "2") (pinfunction "A_2") (pintype "passive"))
      (node (ref "LD9") (pin "2") (pinfunction "A_2") (pintype "passive"))
      (node (ref "R329") (pin "2") (pinfunction "2_2") (pintype "passive"))
      (node (ref "R337") (pin "2") (pinfunction "2_2") (pintype "passive"))
      (node (ref "R9") (pin "2") (pinfunction "2_2") (pintype "passive"))
    )
    (net (code "65") (name "unconnected-(IC41A-CLK125-Pad9)") (class "Default")
      (node (ref "IC41") (pin "9") (pinfunction "CLK125_9") (pintype "output"))
    )
    (net (code "66") (name "unconnected-(IC41A-HSDACN-Pad31)") (class "Default")
      (node (ref "IC41") (pin "31") (pinfunction "HSDACN_31") (pintype "output"))
    )
    (net (code "67") (name "unconnected-(IC41A-HSDACP-Pad32)") (class "Default")
      (node (ref "IC41") (pin "32") (pinfunction "HSDACP_32") (pintype "output"))
    )
    (net (code "68") (name "unconnected-(IC41A-TSTPT-Pad29)") (class "Default")
      (node (ref "IC41") (pin "29") (pinfunction "TSTPT_29") (pintype "output"))
    )
    (net (code "69") (name "unconnected-(J9-Pad14)") (class "Default")
      (node (ref "J9") (pin "14") (pinfunction "14_14") (pintype "bidirectional"))
    )
  )
)
